# 8xbc817.net
KiCad netlist of a schematic drawn in EAGLE
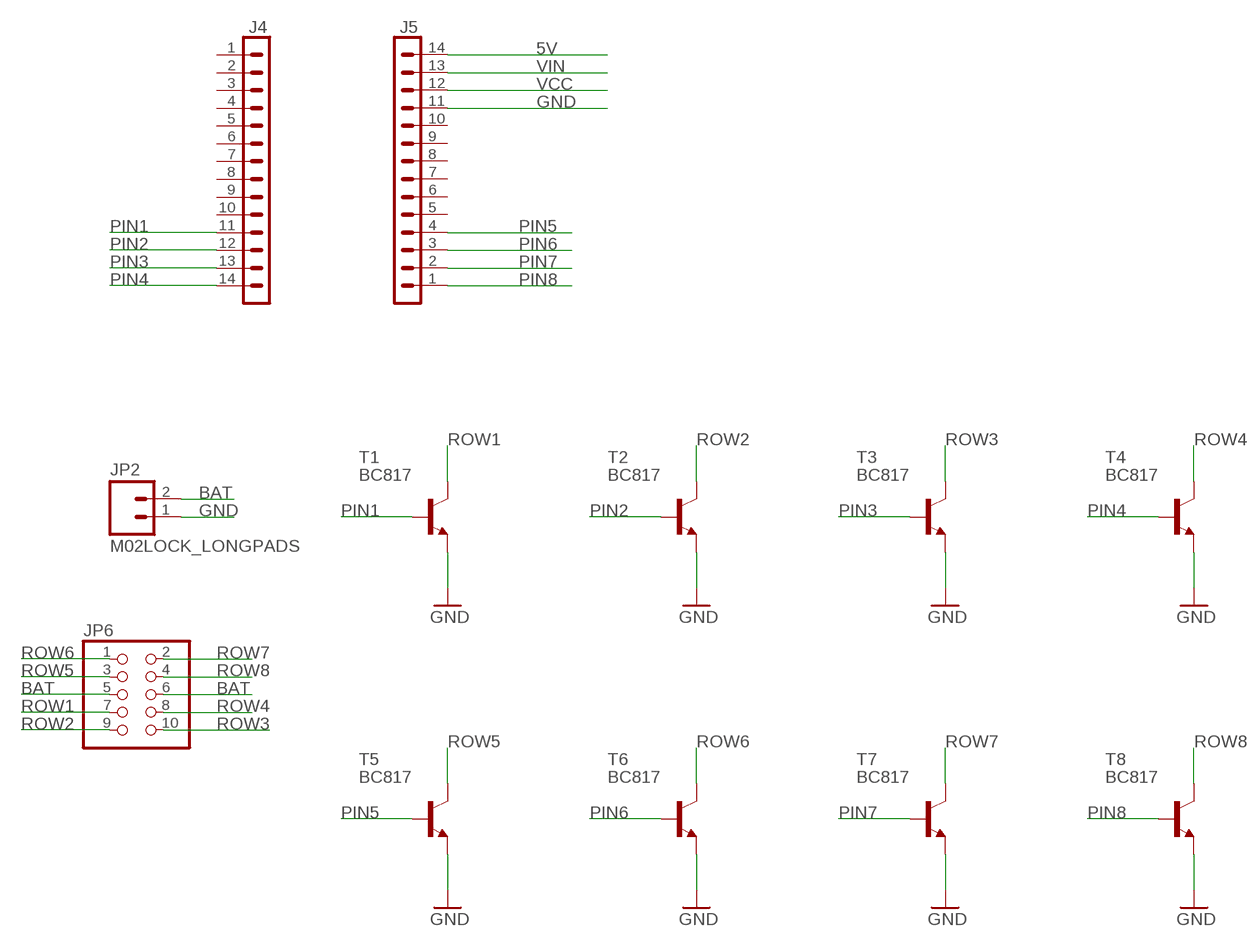
[diagram p0: schematic, sheet 1]

(export (version "E")
  (design (tool "Eeschema 10.0.6"))
  (components
    (comp (ref "J4")
      (value "DNP")
      (footprint "eagle-import:STRIP-14-MODULI-A11")
      (libsource (lib "eagle-import") (part "STRIP-14"))
    )
    (comp (ref "J5")
      (value "DNP")
      (footprint "eagle-import:STRIP-14-MODULI-A11")
      (libsource (lib "eagle-import") (part "STRIP-14"))
    )
    (comp (ref "JP2")
      (value "M02LOCK_LONGPADS")
      (footprint "eagle-import:1X02_LOCK_LONGPADS")
      (libsource (lib "eagle-import") (part "M02LOCK_LONGPADS"))
    )
    (comp (ref "JP6")
      (value "PINHD-2X5")
      (footprint "eagle-import:2X05")
      (libsource (lib "eagle-import") (part "PINHD-2X5"))
    )
    (comp (ref "T1")
      (value "BC817")
      (footprint "eagle-import:SOT23")
      (libsource (lib "eagle-import") (part "BC847"))
    )
    (comp (ref "T2")
      (value "BC817")
      (footprint "eagle-import:SOT23")
      (libsource (lib "eagle-import") (part "BC847"))
    )
    (comp (ref "T3")
      (value "BC817")
      (footprint "eagle-import:SOT23")
      (libsource (lib "eagle-import") (part "BC847"))
    )
    (comp (ref "T4")
      (value "BC817")
      (footprint "eagle-import:SOT23")
      (libsource (lib "eagle-import") (part "BC847"))
    )
    (comp (ref "T5")
      (value "BC817")
      (footprint "eagle-import:SOT23")
      (libsource (lib "eagle-import") (part "BC847"))
    )
    (comp (ref "T6")
      (value "BC817")
      (footprint "eagle-import:SOT23")
      (libsource (lib "eagle-import") (part "BC847"))
    )
    (comp (ref "T7")
      (value "BC817")
      (footprint "eagle-import:SOT23")
      (libsource (lib "eagle-import") (part "BC847"))
    )
    (comp (ref "T8")
      (value "BC817")
      (footprint "eagle-import:SOT23")
      (libsource (lib "eagle-import") (part "BC847"))
    )
  )
  (nets
    (net (code "1") (name "/5V") (class "Default")
      (node (ref "J5") (pin "14") (pinfunction "14_14") (pintype "passive"))
    )
    (net (code "2") (name "/BAT") (class "Default")
      (node (ref "JP2") (pin "2") (pinfunction "2_2") (pintype "passive"))
      (node (ref "JP6") (pin "5") (pinfunction "5_5") (pintype "passive"))
      (node (ref "JP6") (pin "6") (pinfunction "6_6") (pintype "passive"))
    )
    (net (code "3") (name "/PIN1") (class "Default")
      (node (ref "J4") (pin "11") (pinfunction "11_11") (pintype "passive"))
      (node (ref "T1") (pin "1") (pinfunction "B_1") (pintype "passive"))
    )
    (net (code "4") (name "/PIN2") (class "Default")
      (node (ref "J4") (pin "12") (pinfunction "12_12") (pintype "passive"))
      (node (ref "T2") (pin "1") (pinfunction "B_1") (pintype "passive"))
    )
    (net (code "5") (name "/PIN3") (class "Default")
      (node (ref "J4") (pin "13") (pinfunction "13_13") (pintype "passive"))
      (node (ref "T3") (pin "1") (pinfunction "B_1") (pintype "passive"))
    )
    (net (code "6") (name "/PIN4") (class "Default")
      (node (ref "J4") (pin "14") (pinfunction "14_14") (pintype "passive"))
      (node (ref "T4") (pin "1") (pinfunction "B_1") (pintype "passive"))
    )
    (net (code "7") (name "/PIN5") (class "Default")
      (node (ref "J5") (pin "4") (pinfunction "4_4") (pintype "passive"))
      (node (ref "T5") (pin "1") (pinfunction "B_1") (pintype "passive"))
    )
    (net (code "8") (name "/PIN6") (class "Default")
      (node (ref "J5") (pin "3") (pinfunction "3_3") (pintype "passive"))
      (node (ref "T6") (pin "1") (pinfunction "B_1") (pintype "passive"))
    )
    (net (code "9") (name "/PIN7") (class "Default")
      (node (ref "J5") (pin "2") (pinfunction "2_2") (pintype "passive"))
      (node (ref "T7") (pin "1") (pinfunction "B_1") (pintype "passive"))
    )
    (net (code "10") (name "/PIN8") (class "Default")
      (node (ref "J5") (pin "1") (pinfunction "1_1") (pintype "passive"))
      (node (ref "T8") (pin "1") (pinfunction "B_1") (pintype "passive"))
    )
    (net (code "11") (name "/ROW1") (class "Default")
      (node (ref "JP6") (pin "7") (pinfunction "7_7") (pintype "passive"))
      (node (ref "T1") (pin "3") (pinfunction "C_3") (pintype "passive"))
    )
    (net (code "12") (name "/ROW2") (class "Default")
      (node (ref "JP6") (pin "9") (pinfunction "9_9") (pintype "passive"))
      (node (ref "T2") (pin "3") (pinfunction "C_3") (pintype "passive"))
    )
    (net (code "13") (name "/ROW3") (class "Default")
      (node (ref "JP6") (pin "10") (pinfunction "10_10") (pintype "passive"))
      (node (ref "T3") (pin "3") (pinfunction "C_3") (pintype "passive"))
    )
    (net (code "14") (name "/ROW4") (class "Default")
      (node (ref "JP6") (pin "8") (pinfunction "8_8") (pintype "passive"))
      (node (ref "T4") (pin "3") (pinfunction "C_3") (pintype "passive"))
    )
    (net (code "15") (name "/ROW5") (class "Default")
      (node (ref "JP6") (pin "3") (pinfunction "3_3") (pintype "passive"))
      (node (ref "T5") (pin "3") (pinfunction "C_3") (pintype "passive"))
    )
    (net (code "16") (name "/ROW6") (class "Default")
      (node (ref "JP6") (pin "1") (pinfunction "1_1") (pintype "passive"))
      (node (ref "T6") (pin "3") (pinfunction "C_3") (pintype "passive"))
    )
    (net (code "17") (name "/ROW7") (class "Default")
      (node (ref "JP6") (pin "2") (pinfunction "2_2") (pintype "passive"))
      (node (ref "T7") (pin "3") (pinfunction "C_3") (pintype "passive"))
    )
    (net (code "18") (name "/ROW8") (class "Default")
      (node (ref "JP6") (pin "4") (pinfunction "4_4") (pintype "passive"))
      (node (ref "T8") (pin "3") (pinfunction "C_3") (pintype "passive"))
    )
    (net (code "19") (name "/VCC") (class "Default")
      (node (ref "J5") (pin "12") (pinfunction "12_12") (pintype "passive"))
    )
    (net (code "20") (name "/VIN") (class "Default")
      (node (ref "J5") (pin "13") (pinfunction "13_13") (pintype "passive"))
    )
    (net (code "21") (name "GND") (class "Default")
      (node (ref "J5") (pin "11") (pinfunction "11_11") (pintype "passive"))
      (node (ref "JP2") (pin "1") (pinfunction "1_1") (pintype "passive"))
      (node (ref "T1") (pin "2") (pinfunction "E_2") (pintype "passive"))
      (node (ref "T2") (pin "2") (pinfunction "E_2") (pintype "passive"))
      (node (ref "T3") (pin "2") (pinfunction "E_2") (pintype "passive"))
      (node (ref "T4") (pin "2") (pinfunction "E_2") (pintype "passive"))
      (node (ref "T5") (pin "2") (pinfunction "E_2") (pintype "passive"))
      (node (ref "T6") (pin "2") (pinfunction "E_2") (pintype "passive"))
      (node (ref "T7") (pin "2") (pinfunction "E_2") (pintype "passive"))
      (node (ref "T8") (pin "2") (pinfunction "E_2") (pintype "passive"))
    )
    (net (code "22") (name "unconnected-(J4-Pad1)") (class "Default")
      (node (ref "J4") (pin "1") (pinfunction "1_1") (pintype "passive"))
    )
    (net (code "23") (name "unconnected-(J4-Pad2)") (class "Default")
      (node (ref "J4") (pin "2") (pinfunction "2_2") (pintype "passive"))
    )
    (net (code "24") (name "unconnected-(J4-Pad3)") (class "Default")
      (node (ref "J4") (pin "3") (pinfunction "3_3") (pintype "passive"))
    )
    (net (code "25") (name "unconnected-(J4-Pad4)") (class "Default")
      (node (ref "J4") (pin "4") (pinfunction "4_4") (pintype "passive"))
    )
    (net (code "26") (name "unconnected-(J4-Pad5)") (class "Default")
      (node (ref "J4") (pin "5") (pinfunction "5_5") (pintype "passive"))
    )
    (net (code "27") (name "unconnected-(J4-Pad6)") (class "Default")
      (node (ref "J4") (pin "6") (pinfunction "6_6") (pintype "passive"))
    )
    (net (code "28") (name "unconnected-(J4-Pad7)") (class "Default")
      (node (ref "J4") (pin "7") (pinfunction "7_7") (pintype "passive"))
    )
    (net (code "29") (name "unconnected-(J4-Pad8)") (class "Default")
      (node (ref "J4") (pin "8") (pinfunction "8_8") (pintype "passive"))
    )
    (net (code "30") (name "unconnected-(J4-Pad9)") (class "Default")
      (node (ref "J4") (pin "9") (pinfunction "9_9") (pintype "passive"))
    )
    (net (code "31") (name "unconnected-(J4-Pad10)") (class "Default")
      (node (ref "J4") (pin "10") (pinfunction "10_10") (pintype "passive"))
    )
    (net (code "32") (name "unconnected-(J5-Pad5)") (class "Default")
      (node (ref "J5") (pin "5") (pinfunction "5_5") (pintype "passive"))
    )
    (net (code "33") (name "unconnected-(J5-Pad6)") (class "Default")
      (node (ref "J5") (pin "6") (pinfunction "6_6") (pintype "passive"))
    )
    (net (code "34") (name "unconnected-(J5-Pad7)") (class "Default")
      (node (ref "J5") (pin "7") (pinfunction "7_7") (pintype "passive"))
    )
    (net (code "35") (name "unconnected-(J5-Pad8)") (class "Default")
      (node (ref "J5") (pin "8") (pinfunction "8_8") (pintype "passive"))
    )
    (net (code "36") (name "unconnected-(J5-Pad9)") (class "Default")
      (node (ref "J5") (pin "9") (pinfunction "9_9") (pintype "passive"))
    )
    (net (code "37") (name "unconnected-(J5-Pad10)") (class "Default")
      (node (ref "J5") (pin "10") (pinfunction "10_10") (pintype "passive"))
    )
  )
)
